# Sensor_board_2_V_1_0.net
KiCad netlist of a schematic drawn in EAGLE
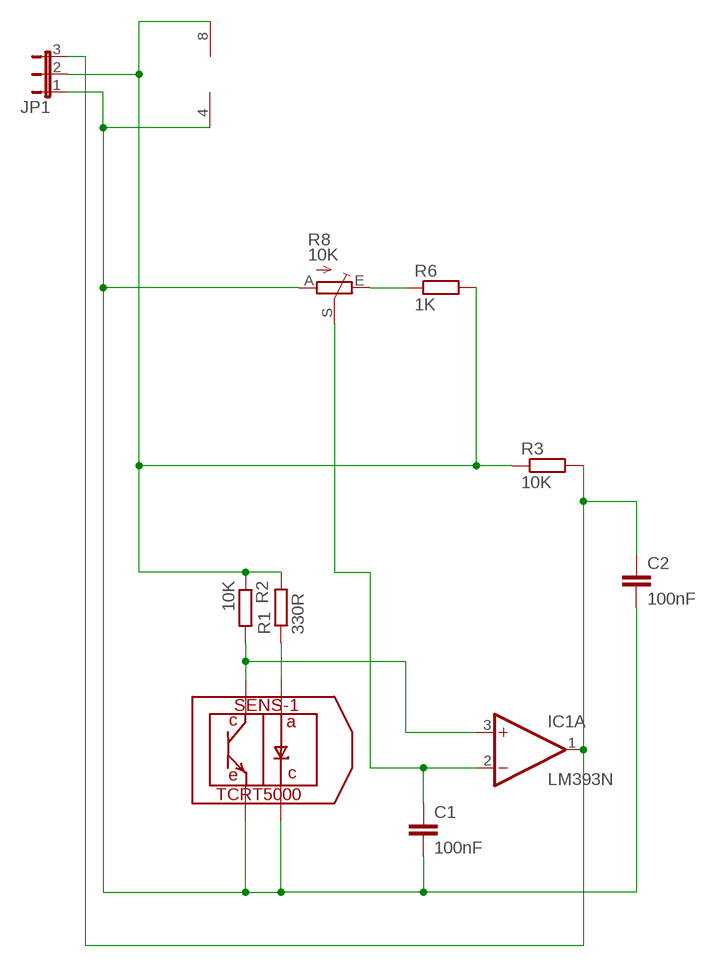
[diagram p0: schematic, sheet 1]

(export (version "E")
  (design (tool "Eeschema 10.0.6"))
  (components
    (comp (ref "C1")
      (value "100nF")
      (footprint "eagle-import:C025_050-025X075")
      (libsource (lib "eagle-import") (part "C-EU025_050-025X075"))
    )
    (comp (ref "C2")
      (value "100nF")
      (footprint "eagle-import:C025_050-025X075")
      (libsource (lib "eagle-import") (part "C-EU025_050-025X075"))
    )
    (comp (ref "IC1")
      (value "LM393N")
      (footprint "eagle-import:DIL08")
      (libsource (lib "eagle-import") (part "LM393N"))
    )
    (comp (ref "JP1")
      (value "JP2E")
      (footprint "eagle-import:JP2")
      (libsource (lib "eagle-import") (part "JP2E"))
    )
    (comp (ref "R1")
      (value "330R")
      (footprint "eagle-import:0309_10")
      (libsource (lib "eagle-import") (part "R-EU_0309/10"))
    )
    (comp (ref "R2")
      (value "10K")
      (footprint "eagle-import:0309_10")
      (libsource (lib "eagle-import") (part "R-EU_0309/10"))
    )
    (comp (ref "R3")
      (value "10K")
      (footprint "eagle-import:0309_10")
      (libsource (lib "eagle-import") (part "R-EU_0309/10"))
    )
    (comp (ref "R6")
      (value "1K")
      (footprint "eagle-import:0309_10")
      (libsource (lib "eagle-import") (part "R-EU_0309/10"))
    )
    (comp (ref "R8")
      (value "10K")
      (footprint "eagle-import:B64Y")
      (libsource (lib "eagle-import") (part "TRIM_EU-B64Y"))
    )
    (comp (ref "SENS-1")
      (value "TCRT5000")
      (footprint "eagle-import:5000")
      (libsource (lib "eagle-import") (part "TCRT5000"))
    )
  )
  (nets
    (net (code "1") (name "Net-(IC1A-+IN)") (class "Default")
      (node (ref "IC1") (pin "3") (pinfunction "+IN_3") (pintype "input"))
      (node (ref "R2") (pin "2") (pinfunction "2_2") (pintype "passive"))
      (node (ref "SENS-1") (pin "P$1") (pinfunction "P$1_P$1") (pintype "passive"))
    )
    (net (code "2") (name "Net-(IC1A--IN)") (class "Default")
      (node (ref "C1") (pin "1") (pinfunction "1_1") (pintype "passive"))
      (node (ref "IC1") (pin "2") (pinfunction "-IN_2") (pintype "input"))
      (node (ref "R8") (pin "S") (pinfunction "S_S") (pintype "passive"))
    )
    (net (code "3") (name "Net-(IC1A-OUT)") (class "Default")
      (node (ref "C2") (pin "1") (pinfunction "1_1") (pintype "passive"))
      (node (ref "IC1") (pin "1") (pinfunction "OUT_1") (pintype "output"))
      (node (ref "JP1") (pin "3") (pinfunction "3_3") (pintype "passive"))
      (node (ref "R3") (pin "2") (pinfunction "2_2") (pintype "passive"))
    )
    (net (code "4") (name "Net-(IC1C-V+)") (class "Default")
      (node (ref "IC1") (pin "8") (pinfunction "V+_8") (pintype "power_in"))
      (node (ref "JP1") (pin "2") (pinfunction "2_2") (pintype "passive"))
      (node (ref "R1") (pin "2") (pinfunction "2_2") (pintype "passive"))
      (node (ref "R2") (pin "1") (pinfunction "1_1") (pintype "passive"))
      (node (ref "R3") (pin "1") (pinfunction "1_1") (pintype "passive"))
      (node (ref "R6") (pin "2") (pinfunction "2_2") (pintype "passive"))
    )
    (net (code "5") (name "Net-(IC1C-V-)") (class "Default")
      (node (ref "C1") (pin "2") (pinfunction "2_2") (pintype "passive"))
      (node (ref "C2") (pin "2") (pinfunction "2_2") (pintype "passive"))
      (node (ref "IC1") (pin "4") (pinfunction "V-_4") (pintype "power_in"))
      (node (ref "JP1") (pin "1") (pinfunction "1_1") (pintype "passive"))
      (node (ref "R8") (pin "A") (pinfunction "A_A") (pintype "passive"))
      (node (ref "SENS-1") (pin "P$2") (pinfunction "P$2_P$2") (pintype "passive"))
      (node (ref "SENS-1") (pin "P$4") (pinfunction "P$4_P$4") (pintype "passive"))
    )
    (net (code "6") (name "Net-(R1-Pad1)") (class "Default")
      (node (ref "R1") (pin "1") (pinfunction "1_1") (pintype "passive"))
      (node (ref "SENS-1") (pin "P$3") (pinfunction "P$3_P$3") (pintype "passive"))
    )
    (net (code "7") (name "Net-(R6-Pad1)") (class "Default")
      (node (ref "R6") (pin "1") (pinfunction "1_1") (pintype "passive"))
      (node (ref "R8") (pin "E") (pinfunction "E_E") (pintype "passive"))
    )
  )
)
